# e202var-receiver-v1.net
KiCad netlist of a schematic drawn in EAGLE
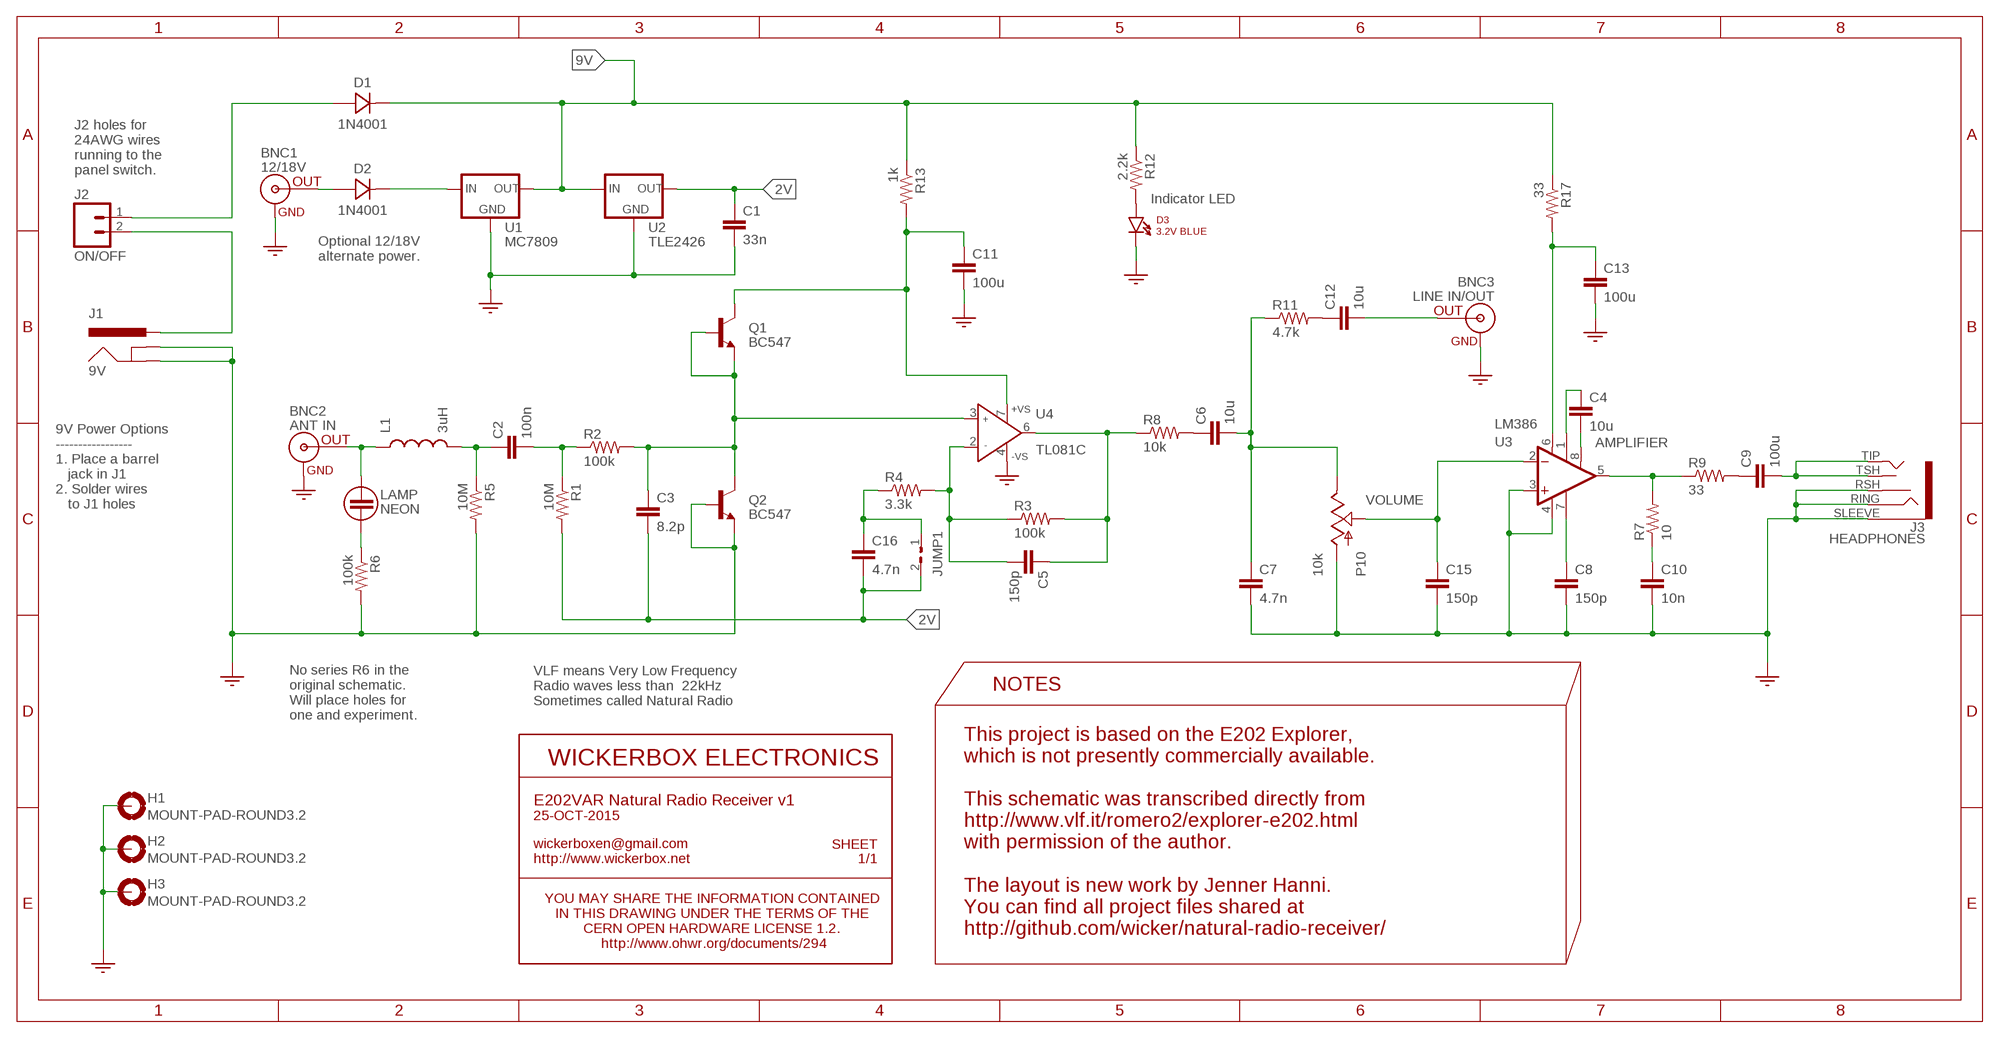
[diagram p0: schematic, sheet 1]

(export (version "E")
  (design (tool "Eeschema 10.0.6"))
  (components
    (comp (ref "BNC1")
      (value "12/18V")
      (footprint "eagle-import:BNC-MOLEX-SD-73100")
      (libsource (lib "eagle-import") (part "BNC-MOLEX-SD-73100"))
    )
    (comp (ref "BNC2")
      (value "ANT IN")
      (footprint "eagle-import:BNC-MOLEX-SD-73100")
      (libsource (lib "eagle-import") (part "BNC-MOLEX-SD-73100"))
    )
    (comp (ref "BNC3")
      (value "LINE IN/OUT")
      (footprint "eagle-import:BNC-MOLEX-SD-73100")
      (libsource (lib "eagle-import") (part "BNC-MOLEX-SD-73100"))
    )
    (comp (ref "C1")
      (value "33n")
      (footprint "eagle-import:CAP-RADIAL-5MM-NONPOL")
      (libsource (lib "eagle-import") (part "CAPACITOR5MM"))
    )
    (comp (ref "C2")
      (value "100n")
      (footprint "eagle-import:CAP-RADIAL-5MM-NONPOL")
      (libsource (lib "eagle-import") (part "CAPACITOR5MM"))
    )
    (comp (ref "C3")
      (value "8.2p")
      (footprint "eagle-import:CAP-RADIAL-5MM-NONPOL")
      (libsource (lib "eagle-import") (part "CAPACITOR5MM"))
    )
    (comp (ref "C4")
      (value "10u")
      (footprint "eagle-import:CAP-RADIAL-2.5MM-NONPOL")
      (libsource (lib "eagle-import") (part "CAPACITOR2.5MM"))
    )
    (comp (ref "C5")
      (value "150p")
      (footprint "eagle-import:CAP-RADIAL-2.5MM-NONPOL")
      (libsource (lib "eagle-import") (part "CAPACITOR2.5MM"))
    )
    (comp (ref "C6")
      (value "10u")
      (footprint "eagle-import:CAP-RADIAL-2.5MM-NONPOL")
      (libsource (lib "eagle-import") (part "CAPACITOR2.5MM"))
    )
    (comp (ref "C7")
      (value "4.7n")
      (footprint "eagle-import:CAP-RADIAL-5MM-NONPOL")
      (libsource (lib "eagle-import") (part "CAPACITOR5MM"))
    )
    (comp (ref "C8")
      (value "150p")
      (footprint "eagle-import:CAP-RADIAL-2.5MM-NONPOL")
      (libsource (lib "eagle-import") (part "CAPACITOR2.5MM"))
    )
    (comp (ref "C9")
      (value "100u")
      (footprint "eagle-import:CAP-RADIAL-5MM-NONPOL")
      (libsource (lib "eagle-import") (part "CAPACITOR5MM"))
    )
    (comp (ref "C10")
      (value "10n")
      (footprint "eagle-import:CAP-RADIAL-2.5MM-NONPOL")
      (libsource (lib "eagle-import") (part "CAPACITOR2.5MM"))
    )
    (comp (ref "C11")
      (value "100u")
      (footprint "eagle-import:CAP-RADIAL-5MM-NONPOL")
      (libsource (lib "eagle-import") (part "CAPACITOR5MM"))
    )
    (comp (ref "C12")
      (value "10u")
      (footprint "eagle-import:CAP-RADIAL-2.5MM-NONPOL")
      (libsource (lib "eagle-import") (part "CAPACITOR2.5MM"))
    )
    (comp (ref "C13")
      (value "100u")
      (footprint "eagle-import:CAP-RADIAL-5MM-NONPOL")
      (libsource (lib "eagle-import") (part "CAPACITOR5MM"))
    )
    (comp (ref "C15")
      (value "150p")
      (footprint "eagle-import:CAP-RADIAL-2.5MM-NONPOL")
      (libsource (lib "eagle-import") (part "CAPACITOR2.5MM"))
    )
    (comp (ref "C16")
      (value "4.7n")
      (footprint "eagle-import:CAP-RADIAL-5MM-NONPOL")
      (libsource (lib "eagle-import") (part "CAPACITOR5MM"))
    )
    (comp (ref "D1")
      (value "1N4001")
      (footprint "eagle-import:DIODE-DO41")
      (libsource (lib "eagle-import") (part "DIODE"))
    )
    (comp (ref "D2")
      (value "1N4001")
      (footprint "eagle-import:DIODE-DO41")
      (libsource (lib "eagle-import") (part "DIODE"))
    )
    (comp (ref "D3")
      (value "3.2V BLUE")
      (footprint "eagle-import:LED-2PIN-0.1IN")
      (libsource (lib "eagle-import") (part "LED"))
    )
    (comp (ref "H1")
      (value "MOUNT-PAD-ROUND3.2")
      (footprint "eagle-import:3,2-PAD")
      (libsource (lib "eagle-import") (part "MOUNT-PAD-ROUND3.2"))
    )
    (comp (ref "H2")
      (value "MOUNT-PAD-ROUND3.2")
      (footprint "eagle-import:3,2-PAD")
      (libsource (lib "eagle-import") (part "MOUNT-PAD-ROUND3.2"))
    )
    (comp (ref "H3")
      (value "MOUNT-PAD-ROUND3.2")
      (footprint "eagle-import:3,2-PAD")
      (libsource (lib "eagle-import") (part "MOUNT-PAD-ROUND3.2"))
    )
    (comp (ref "J1")
      (value "9V")
      (footprint "eagle-import:JACK-POWER")
      (libsource (lib "eagle-import") (part "JACK-POWER-BARREL"))
    )
    (comp (ref "J2")
      (value "ON/OFF")
      (footprint "eagle-import:CONN-2PIN-0.1IN")
      (libsource (lib "eagle-import") (part "CONN-2PIN"))
    )
    (comp (ref "J3")
      (value "HEADPHONES")
      (footprint "eagle-import:JACK-AUDIO-5PIN")
      (libsource (lib "eagle-import") (part "JACK-AUDIO"))
    )
    (comp (ref "JUMP1")
      (value "HPF")
      (footprint "eagle-import:CONN-2PIN-0.1IN")
      (libsource (lib "eagle-import") (part "JUMPER-SHUNT"))
    )
    (comp (ref "L1")
      (value "3uH")
      (footprint "eagle-import:RES-CF14-TH")
      (libsource (lib "eagle-import") (part "INDUCTOR"))
    )
    (comp (ref "LAMP")
      (value "NEON")
      (footprint "eagle-import:LAMP-2PIN-0.1IN")
      (libsource (lib "eagle-import") (part "LAMP-NEON"))
    )
    (comp (ref "P10")
      (value "10k")
      (footprint "eagle-import:POT-3PIN-LINEAR")
      (libsource (lib "eagle-import") (part "POT-P160KN-0QC15B10K"))
    )
    (comp (ref "Q1")
      (value "BC547")
      (footprint "eagle-import:TO-92-AMMO")
      (libsource (lib "eagle-import") (part "BJT-NPN"))
    )
    (comp (ref "Q2")
      (value "BC547")
      (footprint "eagle-import:TO-92-AMMO")
      (libsource (lib "eagle-import") (part "BJT-NPN"))
    )
    (comp (ref "R1")
      (value "10M")
      (footprint "eagle-import:RES-CF14-TH")
      (libsource (lib "eagle-import") (part "RESISTOR"))
    )
    (comp (ref "R2")
      (value "100k")
      (footprint "eagle-import:RES-CF14-TH")
      (libsource (lib "eagle-import") (part "RESISTOR"))
    )
    (comp (ref "R3")
      (value "100k")
      (footprint "eagle-import:RES-CF14-TH")
      (libsource (lib "eagle-import") (part "RESISTOR"))
    )
    (comp (ref "R4")
      (value "3.3k")
      (footprint "eagle-import:RES-CF14-TH")
      (libsource (lib "eagle-import") (part "RESISTOR"))
    )
    (comp (ref "R5")
      (value "10M")
      (footprint "eagle-import:RES-CF14-TH")
      (libsource (lib "eagle-import") (part "RESISTOR"))
    )
    (comp (ref "R6")
      (value "100k")
      (footprint "eagle-import:RES-CF14-TH")
      (libsource (lib "eagle-import") (part "RESISTOR"))
    )
    (comp (ref "R7")
      (value "10")
      (footprint "eagle-import:RES-CF14-TH")
      (libsource (lib "eagle-import") (part "RESISTOR"))
    )
    (comp (ref "R8")
      (value "10k")
      (footprint "eagle-import:RES-CF14-TH")
      (libsource (lib "eagle-import") (part "RESISTOR"))
    )
    (comp (ref "R9")
      (value "33")
      (footprint "eagle-import:RES-CF14-TH")
      (libsource (lib "eagle-import") (part "RESISTOR"))
    )
    (comp (ref "R11")
      (value "4.7k")
      (footprint "eagle-import:RES-CF14-TH")
      (libsource (lib "eagle-import") (part "RESISTOR"))
    )
    (comp (ref "R12")
      (value "2.2k")
      (footprint "eagle-import:RES-CF14-TH")
      (libsource (lib "eagle-import") (part "RESISTOR"))
    )
    (comp (ref "R13")
      (value "1k")
      (footprint "eagle-import:RES-CF14-TH")
      (libsource (lib "eagle-import") (part "RESISTOR"))
    )
    (comp (ref "R17")
      (value "33")
      (footprint "eagle-import:RES-CF14-TH")
      (libsource (lib "eagle-import") (part "RESISTOR"))
    )
    (comp (ref "U1")
      (value "MC7809")
      (footprint "eagle-import:TO-220")
      (libsource (lib "eagle-import") (part "VOLTREG-MC7809"))
    )
    (comp (ref "U2")
      (value "TLE2426")
      (footprint "eagle-import:DIP-08")
      (libsource (lib "eagle-import") (part "VOLTREG-TLE2426"))
    )
    (comp (ref "U3")
      (value "LM386")
      (footprint "eagle-import:DIP-08")
      (libsource (lib "eagle-import") (part "AMP-AUDIO-LM386"))
    )
    (comp (ref "U4")
      (value "TL081C")
      (footprint "eagle-import:DIP-08")
      (libsource (lib "eagle-import") (part "AMP-JFET-TL081CP"))
    )
  )
  (nets
    (net (code "1") (name "2V") (class "Default")
      (node (ref "C1") (pin "1") (pinfunction "1_1") (pintype "passive"))
      (node (ref "C16") (pin "2") (pinfunction "2_2") (pintype "passive"))
      (node (ref "C3") (pin "2") (pinfunction "2_2") (pintype "passive"))
      (node (ref "JUMP1") (pin "2") (pinfunction "2_2") (pintype "passive"))
      (node (ref "R1") (pin "P$2") (pinfunction "2_P$2") (pintype "passive"))
      (node (ref "U2") (pin "1") (pinfunction "OUT_1") (pintype "output"))
    )
    (net (code "2") (name "9V") (class "Default")
      (node (ref "D1") (pin "C") (pinfunction "CATHODE_C") (pintype "passive"))
      (node (ref "R12") (pin "P$1") (pinfunction "1_P$1") (pintype "passive"))
      (node (ref "R13") (pin "P$1") (pinfunction "1_P$1") (pintype "passive"))
      (node (ref "R17") (pin "P$1") (pinfunction "1_P$1") (pintype "passive"))
      (node (ref "U1") (pin "OUT") (pinfunction "OUT_OUT") (pintype "output"))
      (node (ref "U2") (pin "3") (pinfunction "IN_3") (pintype "input"))
    )
    (net (code "3") (name "GND") (class "Default")
      (node (ref "BNC1") (pin "GND") (pinfunction "GND_GND") (pintype "bidirectional"))
      (node (ref "BNC1") (pin "GND1") (pinfunction "GND_GND1") (pintype "bidirectional"))
      (node (ref "BNC2") (pin "GND") (pinfunction "GND_GND") (pintype "bidirectional"))
      (node (ref "BNC2") (pin "GND1") (pinfunction "GND_GND1") (pintype "bidirectional"))
      (node (ref "BNC3") (pin "GND") (pinfunction "GND_GND") (pintype "bidirectional"))
      (node (ref "BNC3") (pin "GND1") (pinfunction "GND_GND1") (pintype "bidirectional"))
      (node (ref "C1") (pin "2") (pinfunction "2_2") (pintype "passive"))
      (node (ref "C10") (pin "2") (pinfunction "2_2") (pintype "passive"))
      (node (ref "C11") (pin "2") (pinfunction "2_2") (pintype "passive"))
      (node (ref "C13") (pin "2") (pinfunction "2_2") (pintype "passive"))
      (node (ref "C15") (pin "2") (pinfunction "2_2") (pintype "passive"))
      (node (ref "C7") (pin "2") (pinfunction "2_2") (pintype "passive"))
      (node (ref "C8") (pin "2") (pinfunction "2_2") (pintype "passive"))
      (node (ref "D3") (pin "C") (pinfunction "CATHODE_C") (pintype "bidirectional"))
      (node (ref "H1") (pin "B3,2") (pinfunction "MOUNT_B3,2") (pintype "passive"))
      (node (ref "H2") (pin "B3,2") (pinfunction "MOUNT_B3,2") (pintype "passive"))
      (node (ref "H3") (pin "B3,2") (pinfunction "MOUNT_B3,2") (pintype "passive"))
      (node (ref "J1") (pin "GND") (pinfunction "GND_GND") (pintype "bidirectional"))
      (node (ref "J1") (pin "GNDBREAK") (pinfunction "GNDBREAK_GNDBREAK") (pintype "bidirectional"))
      (node (ref "J3") (pin "RING") (pinfunction "RING_RING") (pintype "bidirectional"))
      (node (ref "J3") (pin "RSH") (pinfunction "RSH_RSH") (pintype "bidirectional"))
      (node (ref "J3") (pin "SLEEVE") (pinfunction "SLEEVE_SLEEVE") (pintype "bidirectional"))
      (node (ref "P10") (pin "1") (pinfunction "A_1") (pintype "passive"))
      (node (ref "Q2") (pin "2") (pinfunction "B_2") (pintype "passive"))
      (node (ref "Q2") (pin "3") (pinfunction "E_3") (pintype "passive"))
      (node (ref "R5") (pin "P$2") (pinfunction "2_P$2") (pintype "passive"))
      (node (ref "R6") (pin "P$2") (pinfunction "2_P$2") (pintype "passive"))
      (node (ref "U1") (pin "GND") (pinfunction "GND_GND") (pintype "input"))
      (node (ref "U2") (pin "2") (pinfunction "GND_2") (pintype "input"))
      (node (ref "U3") (pin "3") (pinfunction "+IN_3") (pintype "input"))
      (node (ref "U3") (pin "4") (pinfunction "V-_4") (pintype "power_in"))
      (node (ref "U4") (pin "4") (pinfunction "-VS_4") (pintype "input"))
    )
    (net (code "4") (name "Net-(BNC1-OUT)") (class "Default")
      (node (ref "BNC1") (pin "SIGNAL") (pinfunction "OUT_SIGNAL") (pintype "bidirectional"))
      (node (ref "D2") (pin "A") (pinfunction "ANODE_A") (pintype "passive"))
    )
    (net (code "5") (name "Net-(BNC2-OUT)") (class "Default")
      (node (ref "BNC2") (pin "SIGNAL") (pinfunction "OUT_SIGNAL") (pintype "bidirectional"))
      (node (ref "L1") (pin "P$1") (pinfunction "1_P$1") (pintype "passive"))
      (node (ref "LAMP") (pin "A") (pinfunction "1_A") (pintype "passive"))
    )
    (net (code "6") (name "Net-(BNC3-OUT)") (class "Default")
      (node (ref "BNC3") (pin "SIGNAL") (pinfunction "OUT_SIGNAL") (pintype "bidirectional"))
      (node (ref "C12") (pin "2") (pinfunction "2_2") (pintype "passive"))
    )
    (net (code "7") (name "Net-(C4-Pad1)") (class "Default")
      (node (ref "C4") (pin "1") (pinfunction "1_1") (pintype "passive"))
      (node (ref "U3") (pin "1") (pinfunction "GAIN_1") (pintype "bidirectional"))
    )
    (net (code "8") (name "Net-(C4-Pad2)") (class "Default")
      (node (ref "C4") (pin "2") (pinfunction "2_2") (pintype "passive"))
      (node (ref "U3") (pin "8") (pinfunction "GAIN_8") (pintype "bidirectional"))
    )
    (net (code "9") (name "Net-(C9-Pad2)") (class "Default")
      (node (ref "C9") (pin "2") (pinfunction "2_2") (pintype "passive"))
      (node (ref "J3") (pin "TIP") (pinfunction "TIP_TIP") (pintype "bidirectional"))
      (node (ref "J3") (pin "TSH") (pinfunction "TSH_TSH") (pintype "bidirectional"))
    )
    (net (code "10") (name "Net-(D1-ANODE)") (class "Default")
      (node (ref "D1") (pin "A") (pinfunction "ANODE_A") (pintype "passive"))
      (node (ref "J2") (pin "1") (pinfunction "1_1") (pintype "passive"))
    )
    (net (code "11") (name "Net-(D2-CATHODE)") (class "Default")
      (node (ref "D2") (pin "C") (pinfunction "CATHODE_C") (pintype "passive"))
      (node (ref "U1") (pin "IN") (pinfunction "IN_IN") (pintype "input"))
    )
    (net (code "12") (name "Net-(D3-ANODE)") (class "Default")
      (node (ref "D3") (pin "A") (pinfunction "ANODE_A") (pintype "bidirectional"))
      (node (ref "R12") (pin "P$2") (pinfunction "2_P$2") (pintype "passive"))
    )
    (net (code "13") (name "Net-(J1-PadPWR)") (class "Default")
      (node (ref "J1") (pin "PWR") (pinfunction "PWR_PWR") (pintype "bidirectional"))
      (node (ref "J2") (pin "2") (pinfunction "2_2") (pintype "passive"))
    )
    (net (code "14") (name "Net-(L1-2)") (class "Default")
      (node (ref "C2") (pin "1") (pinfunction "1_1") (pintype "passive"))
      (node (ref "L1") (pin "P$2") (pinfunction "2_P$2") (pintype "passive"))
      (node (ref "R5") (pin "P$1") (pinfunction "1_P$1") (pintype "passive"))
    )
    (net (code "15") (name "Net-(LAMP-2)") (class "Default")
      (node (ref "LAMP") (pin "C") (pinfunction "2_C") (pintype "passive"))
      (node (ref "R6") (pin "P$1") (pinfunction "1_P$1") (pintype "passive"))
    )
    (net (code "16") (name "Net-(P10-E)") (class "Default")
      (node (ref "C6") (pin "2") (pinfunction "2_2") (pintype "passive"))
      (node (ref "C7") (pin "1") (pinfunction "1_1") (pintype "passive"))
      (node (ref "P10") (pin "3") (pinfunction "E_3") (pintype "passive"))
      (node (ref "R11") (pin "P$1") (pinfunction "1_P$1") (pintype "passive"))
    )
    (net (code "17") (name "Net-(P10-S)") (class "Default")
      (node (ref "C15") (pin "1") (pinfunction "1_1") (pintype "passive"))
      (node (ref "P10") (pin "2") (pinfunction "S_2") (pintype "passive"))
      (node (ref "U3") (pin "2") (pinfunction "-IN_2") (pintype "input"))
    )
    (net (code "18") (name "Net-(Q1-B)") (class "Default")
      (node (ref "C3") (pin "1") (pinfunction "1_1") (pintype "passive"))
      (node (ref "Q1") (pin "2") (pinfunction "B_2") (pintype "passive"))
      (node (ref "Q1") (pin "3") (pinfunction "E_3") (pintype "passive"))
      (node (ref "Q2") (pin "1") (pinfunction "C_1") (pintype "passive"))
      (node (ref "R2") (pin "P$2") (pinfunction "2_P$2") (pintype "passive"))
      (node (ref "U4") (pin "3") (pinfunction "IN+_3") (pintype "input"))
    )
    (net (code "19") (name "Net-(Q1-C)") (class "Default")
      (node (ref "C11") (pin "1") (pinfunction "1_1") (pintype "passive"))
      (node (ref "Q1") (pin "1") (pinfunction "C_1") (pintype "passive"))
      (node (ref "R13") (pin "P$2") (pinfunction "2_P$2") (pintype "passive"))
      (node (ref "U4") (pin "7") (pinfunction "+VS_7") (pintype "input"))
    )
    (net (code "20") (name "Net-(R1-1)") (class "Default")
      (node (ref "C2") (pin "2") (pinfunction "2_2") (pintype "passive"))
      (node (ref "R1") (pin "P$1") (pinfunction "1_P$1") (pintype "passive"))
      (node (ref "R2") (pin "P$1") (pinfunction "1_P$1") (pintype "passive"))
    )
    (net (code "21") (name "Net-(R3-1)") (class "Default")
      (node (ref "C5") (pin "2") (pinfunction "2_2") (pintype "passive"))
      (node (ref "R3") (pin "P$1") (pinfunction "1_P$1") (pintype "passive"))
      (node (ref "R4") (pin "P$2") (pinfunction "2_P$2") (pintype "passive"))
      (node (ref "U4") (pin "2") (pinfunction "IN-_2") (pintype "input"))
    )
    (net (code "22") (name "Net-(R3-2)") (class "Default")
      (node (ref "C5") (pin "1") (pinfunction "1_1") (pintype "passive"))
      (node (ref "R3") (pin "P$2") (pinfunction "2_P$2") (pintype "passive"))
      (node (ref "R8") (pin "P$1") (pinfunction "1_P$1") (pintype "passive"))
      (node (ref "U4") (pin "6") (pinfunction "OUT_6") (pintype "output"))
    )
    (net (code "23") (name "Net-(R4-1)") (class "Default")
      (node (ref "C16") (pin "1") (pinfunction "1_1") (pintype "passive"))
      (node (ref "JUMP1") (pin "1") (pinfunction "1_1") (pintype "passive"))
      (node (ref "R4") (pin "P$1") (pinfunction "1_P$1") (pintype "passive"))
    )
    (net (code "24") (name "Net-(R7-1)") (class "Default")
      (node (ref "C10") (pin "1") (pinfunction "1_1") (pintype "passive"))
      (node (ref "R7") (pin "P$1") (pinfunction "1_P$1") (pintype "passive"))
    )
    (net (code "25") (name "Net-(R7-2)") (class "Default")
      (node (ref "R7") (pin "P$2") (pinfunction "2_P$2") (pintype "passive"))
      (node (ref "R9") (pin "P$1") (pinfunction "1_P$1") (pintype "passive"))
      (node (ref "U3") (pin "5") (pinfunction "OUT_5") (pintype "output"))
    )
    (net (code "26") (name "Net-(R8-2)") (class "Default")
      (node (ref "C6") (pin "1") (pinfunction "1_1") (pintype "passive"))
      (node (ref "R8") (pin "P$2") (pinfunction "2_P$2") (pintype "passive"))
    )
    (net (code "27") (name "Net-(R9-2)") (class "Default")
      (node (ref "C9") (pin "1") (pinfunction "1_1") (pintype "passive"))
      (node (ref "R9") (pin "P$2") (pinfunction "2_P$2") (pintype "passive"))
    )
    (net (code "28") (name "Net-(R11-2)") (class "Default")
      (node (ref "C12") (pin "1") (pinfunction "1_1") (pintype "passive"))
      (node (ref "R11") (pin "P$2") (pinfunction "2_P$2") (pintype "passive"))
    )
    (net (code "29") (name "Net-(R17-2)") (class "Default")
      (node (ref "C13") (pin "1") (pinfunction "1_1") (pintype "passive"))
      (node (ref "R17") (pin "P$2") (pinfunction "2_P$2") (pintype "passive"))
      (node (ref "U3") (pin "6") (pinfunction "V+_6") (pintype "power_in"))
    )
    (net (code "30") (name "Net-(U3-BP)") (class "Default")
      (node (ref "C8") (pin "1") (pinfunction "1_1") (pintype "passive"))
      (node (ref "U3") (pin "7") (pinfunction "BP_7") (pintype "bidirectional"))
    )
  )
)
